# arbc.net
KiCad netlist of a schematic drawn in EAGLE
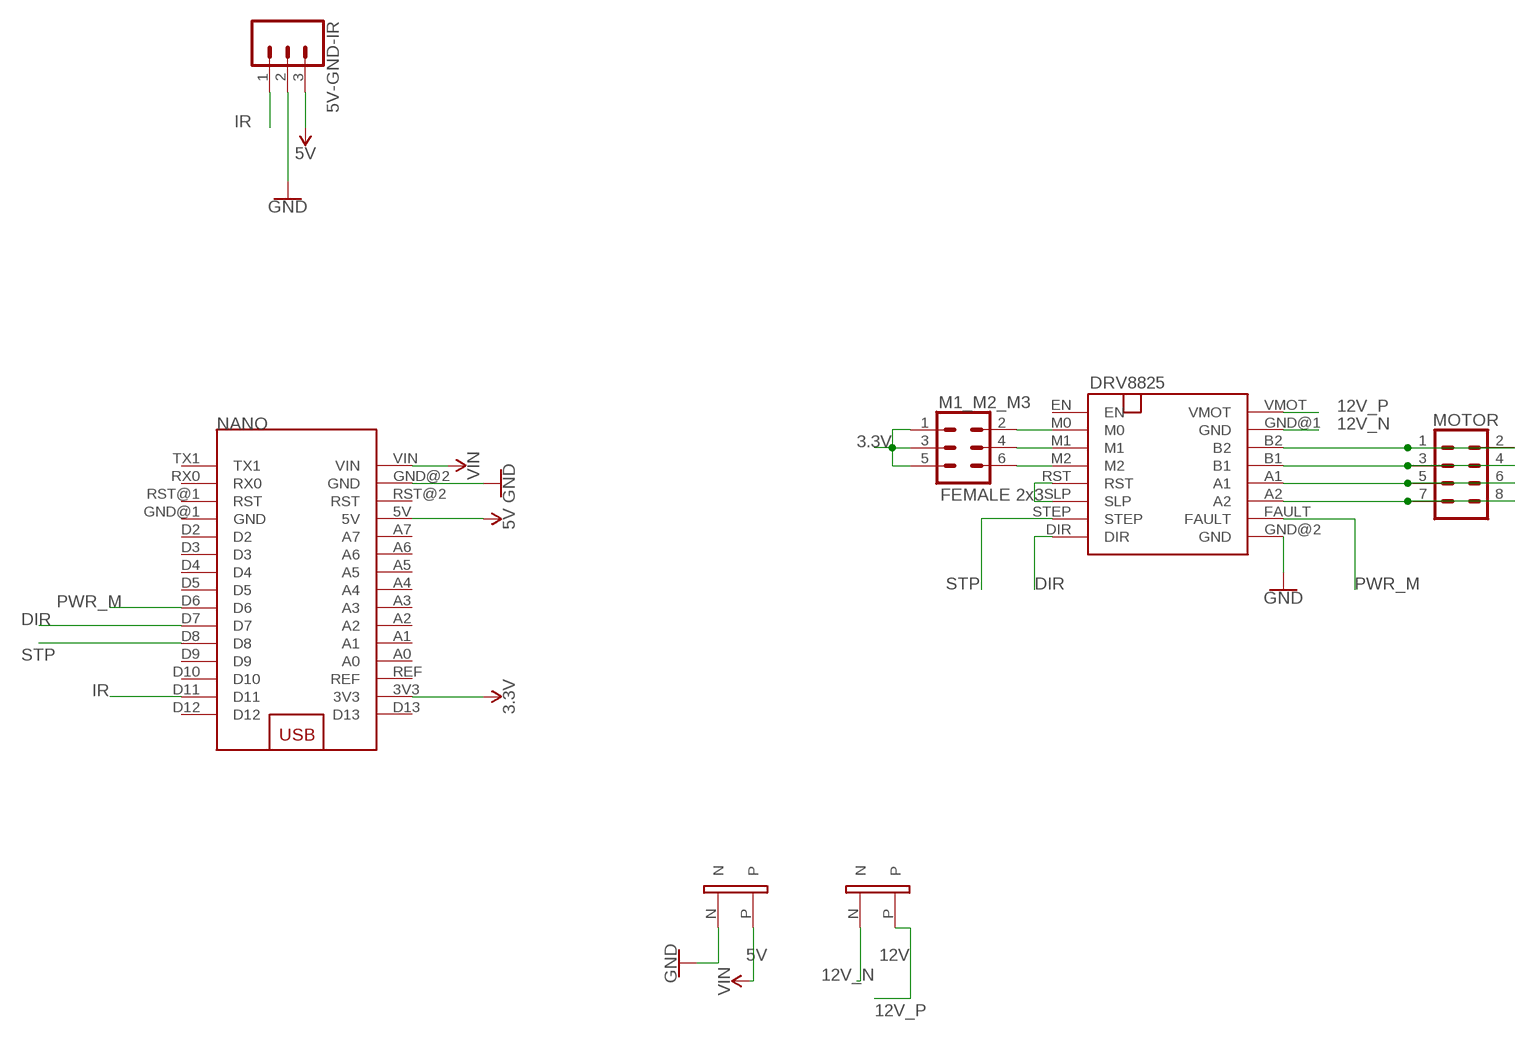
[diagram p0: schematic, sheet 1]

(export (version "E")
  (design (tool "Eeschema 10.0.6"))
  (components
    (comp (ref "5V")
      (value "5MM_CONNECTOR")
      (footprint "eagle-import:5MM_CONNECTOR")
      (libsource (lib "eagle-import") (part "5MM_CONNECTOR"))
    )
    (comp (ref "5V-GND-IR")
      (value "CONN_03")
      (footprint "eagle-import:1X03")
      (libsource (lib "eagle-import") (part "CONN_03"))
    )
    (comp (ref "12V")
      (value "5MM_CONNECTOR")
      (footprint "eagle-import:5MM_CONNECTOR")
      (libsource (lib "eagle-import") (part "5MM_CONNECTOR"))
    )
    (comp (ref "DRV8825")
      (value "DRV8825")
      (footprint "eagle-import:DRV8825")
      (libsource (lib "eagle-import") (part "DRV8825"))
    )
    (comp (ref "M1_M2_M3")
      (value "FEMALE 2x3")
      (footprint "eagle-import:2X3")
      (libsource (lib "eagle-import") (part "CONN_03X2FEMALE"))
    )
    (comp (ref "MOTOR")
      (value "CONN_04X2")
      (footprint "eagle-import:2X4")
      (libsource (lib "eagle-import") (part "CONN_04X2"))
    )
    (comp (ref "NANO")
      (value "ARDUINO_NANO")
      (footprint "eagle-import:ARDUINO_NANO")
      (libsource (lib "eagle-import") (part "ARDUINO_NANO"))
    )
  )
  (nets
    (net (code "1") (name "/12V_N") (class "Default")
      (node (ref "12V") (pin "N") (pinfunction "N_N") (pintype "bidirectional"))
      (node (ref "DRV8825") (pin "GND@1") (pinfunction "GND_GND@1") (pintype "bidirectional"))
    )
    (net (code "2") (name "/12V_P") (class "Default")
      (node (ref "12V") (pin "P") (pinfunction "P_P") (pintype "bidirectional"))
      (node (ref "DRV8825") (pin "VMOT") (pinfunction "VMOT_VMOT") (pintype "bidirectional"))
    )
    (net (code "3") (name "/DIR") (class "Default")
      (node (ref "DRV8825") (pin "DIR") (pinfunction "DIR_DIR") (pintype "bidirectional"))
      (node (ref "NANO") (pin "D7") (pinfunction "D7_D7") (pintype "bidirectional"))
    )
    (net (code "4") (name "/IR") (class "Default")
      (node (ref "5V-GND-IR") (pin "1") (pinfunction "1_1") (pintype "passive"))
      (node (ref "NANO") (pin "D11") (pinfunction "D11_D11") (pintype "bidirectional"))
    )
    (net (code "5") (name "/PWR_M") (class "Default")
      (node (ref "DRV8825") (pin "FAULT") (pinfunction "FAULT_FAULT") (pintype "bidirectional"))
      (node (ref "NANO") (pin "D6") (pinfunction "D6_D6") (pintype "bidirectional"))
    )
    (net (code "6") (name "/STP") (class "Default")
      (node (ref "DRV8825") (pin "STEP") (pinfunction "STEP_STEP") (pintype "bidirectional"))
      (node (ref "NANO") (pin "D8") (pinfunction "D8_D8") (pintype "bidirectional"))
    )
    (net (code "7") (name "3.3V") (class "Default")
      (node (ref "M1_M2_M3") (pin "1") (pinfunction "1_1") (pintype "bidirectional"))
      (node (ref "M1_M2_M3") (pin "3") (pinfunction "3_3") (pintype "bidirectional"))
      (node (ref "M1_M2_M3") (pin "5") (pinfunction "5_5") (pintype "bidirectional"))
      (node (ref "NANO") (pin "3V3") (pinfunction "3V3_3V3") (pintype "bidirectional"))
    )
    (net (code "8") (name "5V") (class "Default")
      (node (ref "5V-GND-IR") (pin "3") (pinfunction "3_3") (pintype "passive"))
      (node (ref "NANO") (pin "5V") (pinfunction "5V_5V") (pintype "bidirectional"))
    )
    (net (code "9") (name "GND") (class "Default")
      (node (ref "5V") (pin "N") (pinfunction "N_N") (pintype "bidirectional"))
      (node (ref "5V-GND-IR") (pin "2") (pinfunction "2_2") (pintype "passive"))
      (node (ref "DRV8825") (pin "GND@2") (pinfunction "GND_GND@2") (pintype "bidirectional"))
      (node (ref "NANO") (pin "GND@2") (pinfunction "GND_GND@2") (pintype "bidirectional"))
    )
    (net (code "10") (name "Net-(DRV8825-PadA1)") (class "Default")
      (node (ref "DRV8825") (pin "A1") (pinfunction "A1_A1") (pintype "bidirectional"))
      (node (ref "MOTOR") (pin "5") (pinfunction "5_5") (pintype "passive"))
      (node (ref "MOTOR") (pin "6") (pinfunction "6_6") (pintype "passive"))
    )
    (net (code "11") (name "Net-(DRV8825-PadA2)") (class "Default")
      (node (ref "DRV8825") (pin "A2") (pinfunction "A2_A2") (pintype "bidirectional"))
      (node (ref "MOTOR") (pin "7") (pinfunction "7_7") (pintype "passive"))
      (node (ref "MOTOR") (pin "8") (pinfunction "8_8") (pintype "passive"))
    )
    (net (code "12") (name "Net-(DRV8825-PadB1)") (class "Default")
      (node (ref "DRV8825") (pin "B1") (pinfunction "B1_B1") (pintype "bidirectional"))
      (node (ref "MOTOR") (pin "3") (pinfunction "3_3") (pintype "passive"))
      (node (ref "MOTOR") (pin "4") (pinfunction "4_4") (pintype "passive"))
    )
    (net (code "13") (name "Net-(DRV8825-PadB2)") (class "Default")
      (node (ref "DRV8825") (pin "B2") (pinfunction "B2_B2") (pintype "bidirectional"))
      (node (ref "MOTOR") (pin "1") (pinfunction "1_1") (pintype "passive"))
      (node (ref "MOTOR") (pin "2") (pinfunction "2_2") (pintype "passive"))
    )
    (net (code "14") (name "Net-(DRV8825-PadM0)") (class "Default")
      (node (ref "DRV8825") (pin "M0") (pinfunction "M0_M0") (pintype "bidirectional"))
      (node (ref "M1_M2_M3") (pin "2") (pinfunction "2_2") (pintype "bidirectional"))
    )
    (net (code "15") (name "Net-(DRV8825-PadM1)") (class "Default")
      (node (ref "DRV8825") (pin "M1") (pinfunction "M1_M1") (pintype "bidirectional"))
      (node (ref "M1_M2_M3") (pin "4") (pinfunction "4_4") (pintype "bidirectional"))
    )
    (net (code "16") (name "Net-(DRV8825-PadM2)") (class "Default")
      (node (ref "DRV8825") (pin "M2") (pinfunction "M2_M2") (pintype "bidirectional"))
      (node (ref "M1_M2_M3") (pin "6") (pinfunction "6_6") (pintype "bidirectional"))
    )
    (net (code "17") (name "Net-(DRV8825-PadRST)") (class "Default")
      (node (ref "DRV8825") (pin "RST") (pinfunction "RST_RST") (pintype "bidirectional"))
      (node (ref "DRV8825") (pin "SLP") (pinfunction "SLP_SLP") (pintype "bidirectional"))
    )
    (net (code "18") (name "VIN") (class "Default")
      (node (ref "5V") (pin "P") (pinfunction "P_P") (pintype "bidirectional"))
      (node (ref "NANO") (pin "VIN") (pinfunction "VIN_VIN") (pintype "bidirectional"))
    )
    (net (code "19") (name "unconnected-(DRV8825-PadEN)") (class "Default")
      (node (ref "DRV8825") (pin "EN") (pinfunction "EN_EN") (pintype "bidirectional"))
    )
    (net (code "20") (name "unconnected-(NANO-GND-PadGND@1)") (class "Default")
      (node (ref "NANO") (pin "GND@1") (pinfunction "GND_GND@1") (pintype "bidirectional"))
    )
    (net (code "21") (name "unconnected-(NANO-PadA0)") (class "Default")
      (node (ref "NANO") (pin "A0") (pinfunction "A0_A0") (pintype "bidirectional"))
    )
    (net (code "22") (name "unconnected-(NANO-PadA1)") (class "Default")
      (node (ref "NANO") (pin "A1") (pinfunction "A1_A1") (pintype "bidirectional"))
    )
    (net (code "23") (name "unconnected-(NANO-PadA2)") (class "Default")
      (node (ref "NANO") (pin "A2") (pinfunction "A2_A2") (pintype "bidirectional"))
    )
    (net (code "24") (name "unconnected-(NANO-PadA3)") (class "Default")
      (node (ref "NANO") (pin "A3") (pinfunction "A3_A3") (pintype "bidirectional"))
    )
    (net (code "25") (name "unconnected-(NANO-PadA4)") (class "Default")
      (node (ref "NANO") (pin "A4") (pinfunction "A4_A4") (pintype "bidirectional"))
    )
    (net (code "26") (name "unconnected-(NANO-PadA5)") (class "Default")
      (node (ref "NANO") (pin "A5") (pinfunction "A5_A5") (pintype "bidirectional"))
    )
    (net (code "27") (name "unconnected-(NANO-PadA6)") (class "Default")
      (node (ref "NANO") (pin "A6") (pinfunction "A6_A6") (pintype "bidirectional"))
    )
    (net (code "28") (name "unconnected-(NANO-PadA7)") (class "Default")
      (node (ref "NANO") (pin "A7") (pinfunction "A7_A7") (pintype "bidirectional"))
    )
    (net (code "29") (name "unconnected-(NANO-PadD2)") (class "Default")
      (node (ref "NANO") (pin "D2") (pinfunction "D2_D2") (pintype "bidirectional"))
    )
    (net (code "30") (name "unconnected-(NANO-PadD3)") (class "Default")
      (node (ref "NANO") (pin "D3") (pinfunction "D3_D3") (pintype "bidirectional"))
    )
    (net (code "31") (name "unconnected-(NANO-PadD4)") (class "Default")
      (node (ref "NANO") (pin "D4") (pinfunction "D4_D4") (pintype "bidirectional"))
    )
    (net (code "32") (name "unconnected-(NANO-PadD5)") (class "Default")
      (node (ref "NANO") (pin "D5") (pinfunction "D5_D5") (pintype "bidirectional"))
    )
    (net (code "33") (name "unconnected-(NANO-PadD9)") (class "Default")
      (node (ref "NANO") (pin "D9") (pinfunction "D9_D9") (pintype "bidirectional"))
    )
    (net (code "34") (name "unconnected-(NANO-PadD10)") (class "Default")
      (node (ref "NANO") (pin "D10") (pinfunction "D10_D10") (pintype "bidirectional"))
    )
    (net (code "35") (name "unconnected-(NANO-PadD12)") (class "Default")
      (node (ref "NANO") (pin "D12") (pinfunction "D12_D12") (pintype "bidirectional"))
    )
    (net (code "36") (name "unconnected-(NANO-PadD13)") (class "Default")
      (node (ref "NANO") (pin "D13") (pinfunction "D13_D13") (pintype "bidirectional"))
    )
    (net (code "37") (name "unconnected-(NANO-PadREF)") (class "Default")
      (node (ref "NANO") (pin "REF") (pinfunction "REF_REF") (pintype "bidirectional"))
    )
    (net (code "38") (name "unconnected-(NANO-PadRX0)") (class "Default")
      (node (ref "NANO") (pin "RX0") (pinfunction "RX0_RX0") (pintype "bidirectional"))
    )
    (net (code "39") (name "unconnected-(NANO-PadTX1)") (class "Default")
      (node (ref "NANO") (pin "TX1") (pinfunction "TX1_TX1") (pintype "bidirectional"))
    )
    (net (code "40") (name "unconnected-(NANO-RST-PadRST@1)") (class "Default")
      (node (ref "NANO") (pin "RST@1") (pinfunction "RST_RST@1") (pintype "bidirectional"))
    )
    (net (code "41") (name "unconnected-(NANO-RST-PadRST@2)") (class "Default")
      (node (ref "NANO") (pin "RST@2") (pinfunction "RST_RST@2") (pintype "bidirectional"))
    )
  )
)
